# TopLevel.net
KiCad netlist of a schematic drawn in Altium Designer
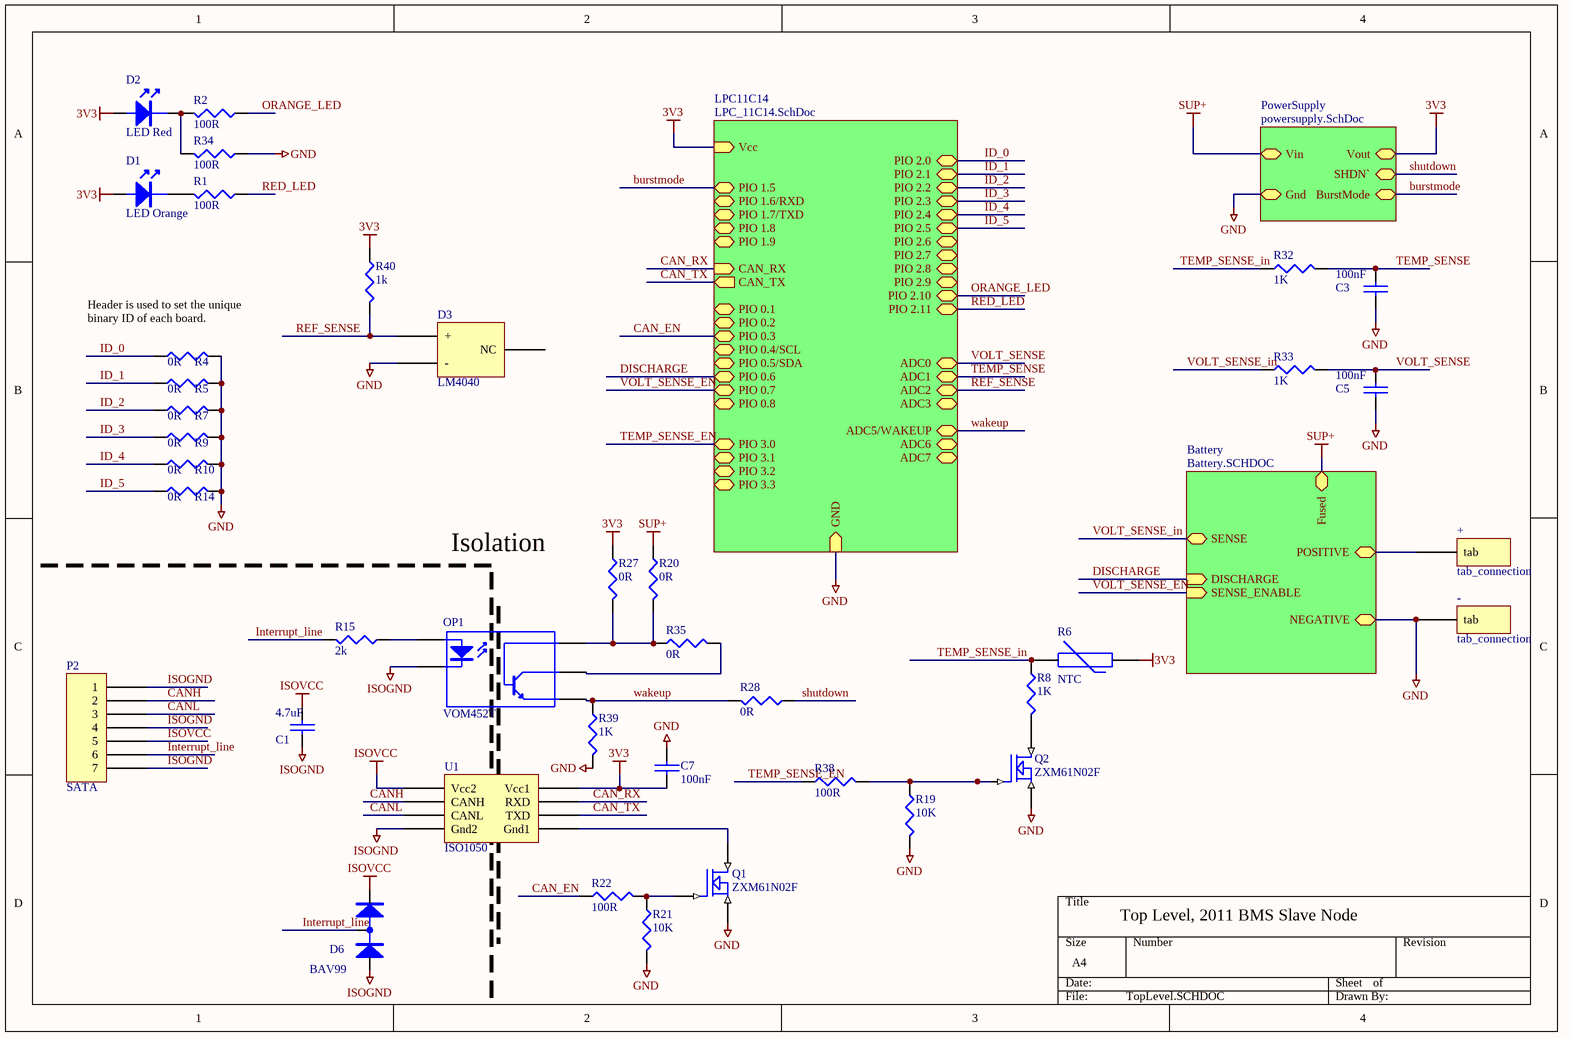
[diagram p0: TopLevel.SCHDOC]

(export (version "E")
  (design (tool "Eeschema 10.0.6"))
  (components
    (comp (ref "+")
      (value "tab_connection")
      (footprint "tab_connect")
      (libsource (lib "BMS") (part "tab_connection"))
    )
    (comp (ref "-")
      (value "tab_connection")
      (footprint "tab_connect")
      (libsource (lib "BMS") (part "tab_connection"))
    )
    (comp (ref "C1")
      (value "4.7uF")
      (footprint "0805")
      (description "Capacitor")
      (libsource (lib "*") (part "CAP"))
    )
    (comp (ref "C3")
      (value "100nF")
      (footprint "0603")
      (description "Capacitor")
      (libsource (lib "*") (part "CAP"))
    )
    (comp (ref "C5")
      (value "100nF")
      (footprint "0603")
      (description "Capacitor")
      (libsource (lib "*") (part "CAP"))
    )
    (comp (ref "C7")
      (value "100nF")
      (footprint "0603")
      (description "Capacitor")
      (libsource (lib "*") (part "CAP"))
    )
    (comp (ref "D1") (value "LED Orange") (footprint "0603_LED") (libsource (lib "SUNSWIFTLIB") (part "LED")))
    (comp (ref "D2")
      (value "LED Red")
      (footprint "0603_LED")
      (libsource (lib "SunswiftLib20030312RR") (part "LED"))
    )
    (comp (ref "D3") (value "LM4040") (footprint "SOT23-3") (libsource (lib "BMS") (part "LM4040")))
    (comp (ref "D6")
      (value "BAV99")
      (footprint "BAV99")
      (description "diode, series connected")
      (libsource (lib "*") (part "DIODE SERIES 2"))
    )
    (comp (ref "OP1") (value "VOM452T") (footprint "VOM452T") (libsource (lib "BMS") (part "VOM452T")))
    (comp (ref "P2") (value "SATA") (footprint "47080-4005-SATA") (libsource (lib "BMS") (part "SATA")))
    (comp (ref "Q1")
      (value "ZXM61N02F")
      (footprint "SOT23-3")
      (description "1.7A, 20V N-Channel Enhancement mode FET")
      (libsource (lib "RCLDQ") (part "ZXM61N02F"))
    )
    (comp (ref "Q2")
      (value "ZXM61N02F")
      (footprint "SOT23-3")
      (description "1.7A, 20V N-Channel Enhancement mode FET")
      (libsource (lib "RCLDQ") (part "ZXM61N02F"))
    )
    (comp (ref "R1")
      (value "100R")
      (footprint "0603")
      (description "Resistor")
      (libsource (lib "SunswiftLib20030312RR") (part "RES1"))
    )
    (comp (ref "R2")
      (value "100R")
      (footprint "0603")
      (description "Resistor")
      (libsource (lib "SunswiftLib20030312RR") (part "RES1"))
    )
    (comp (ref "R4")
      (value "0R")
      (footprint "0603")
      (description "Resistor")
      (libsource (lib "SUNSWIFTLIB") (part "RES1"))
    )
    (comp (ref "R5")
      (value "0R")
      (footprint "0603")
      (description "Resistor")
      (libsource (lib "SUNSWIFTLIB") (part "RES1"))
    )
    (comp (ref "R6")
      (value "NTC")
      (footprint "MHDR1X2")
      (description "Thermistor, NTC")
      (libsource (lib "RCLDQ") (part "NTC"))
    )
    (comp (ref "R7")
      (value "0R")
      (footprint "0603")
      (description "Resistor")
      (libsource (lib "SUNSWIFTLIB") (part "RES1"))
    )
    (comp (ref "R8")
      (value "1K")
      (footprint "0603")
      (description "Resistor")
      (libsource (lib "SUNSWIFTLIB") (part "RES1"))
    )
    (comp (ref "R9")
      (value "0R")
      (footprint "0603")
      (description "Resistor")
      (libsource (lib "SUNSWIFTLIB") (part "RES1"))
    )
    (comp (ref "R10")
      (value "0R")
      (footprint "0603")
      (description "Resistor")
      (libsource (lib "SUNSWIFTLIB") (part "RES1"))
    )
    (comp (ref "R14")
      (value "0R")
      (footprint "0603")
      (description "Resistor")
      (libsource (lib "SUNSWIFTLIB") (part "RES1"))
    )
    (comp (ref "R15")
      (value "2k")
      (footprint "0603")
      (description "Resistor")
      (libsource (lib "RCLDQ") (part "RES1"))
    )
    (comp (ref "R19")
      (value "10K")
      (footprint "0603")
      (description "Resistor")
      (libsource (lib "SUNSWIFTLIB") (part "RES1"))
    )
    (comp (ref "R20")
      (value "0R")
      (footprint "0603")
      (description "Resistor")
      (libsource (lib "RCLDQ") (part "RES1"))
    )
    (comp (ref "R21")
      (value "10K")
      (footprint "0603")
      (description "Resistor")
      (libsource (lib "SUNSWIFTLIB") (part "RES1"))
    )
    (comp (ref "R22")
      (value "100R")
      (footprint "0603")
      (description "Resistor")
      (libsource (lib "SUNSWIFTLIB") (part "RES1"))
    )
    (comp (ref "R27")
      (value "0R")
      (footprint "0603")
      (description "Resistor")
      (libsource (lib "RCLDQ") (part "RES1"))
    )
    (comp (ref "R28")
      (value "0R")
      (footprint "0603")
      (description "Resistor")
      (libsource (lib "RCLDQ") (part "RES1"))
    )
    (comp (ref "R32")
      (value "1K")
      (footprint "0603")
      (description "Resistor")
      (libsource (lib "SUNSWIFTLIB") (part "RES1"))
    )
    (comp (ref "R33")
      (value "1K")
      (footprint "0603")
      (description "Resistor")
      (libsource (lib "SUNSWIFTLIB") (part "RES1"))
    )
    (comp (ref "R34")
      (value "100R")
      (footprint "0603")
      (description "Resistor")
      (libsource (lib "SunswiftLib20030312RR") (part "RES1"))
    )
    (comp (ref "R35")
      (value "0R")
      (footprint "0603")
      (description "Resistor")
      (libsource (lib "RCLDQ") (part "RES1"))
    )
    (comp (ref "R38")
      (value "100R")
      (footprint "0603")
      (description "Resistor")
      (libsource (lib "SUNSWIFTLIB") (part "RES1"))
    )
    (comp (ref "R39")
      (value "1K")
      (footprint "0603")
      (description "Resistor")
      (libsource (lib "RCLDQ") (part "RES1"))
    )
    (comp (ref "R40")
      (value "1k")
      (footprint "0603")
      (description "Resistor")
      (libsource (lib "RCLDQ") (part "RES1"))
    )
    (comp (ref "U1") (value "ISO1050") (footprint "SOP8") (libsource (lib "BMS") (part "ISO1050")))
  )
  (nets
    (net (code "4") (name "/CANH") (class "Default")
      (node (ref "P2") (pin "2") (pinfunction "2_2") (pintype "passive"))
      (node (ref "U1") (pin "7") (pinfunction "CANH_7") (pintype "passive"))
    )
    (net (code "5") (name "/CANL") (class "Default")
      (node (ref "P2") (pin "3") (pinfunction "3_3") (pintype "passive"))
      (node (ref "U1") (pin "6") (pinfunction "CANL_6") (pintype "passive"))
    )
    (net (code "6") (name "/CAN_EN") (class "Default")
      (node (ref "R22") (pin "1") (pinfunction "1_1") (pintype "passive"))
    )
    (net (code "7") (name "/CAN_RX") (class "Default")
      (node (ref "U1") (pin "2") (pinfunction "RXD_2") (pintype "passive"))
    )
    (net (code "8") (name "/CAN_TX") (class "Default")
      (node (ref "U1") (pin "3") (pinfunction "TXD_3") (pintype "passive"))
    )
    (net (code "10") (name "/ID_0") (class "Default")
      (node (ref "R4") (pin "1") (pinfunction "1_1") (pintype "passive"))
    )
    (net (code "11") (name "/ID_1") (class "Default")
      (node (ref "R5") (pin "1") (pinfunction "1_1") (pintype "passive"))
    )
    (net (code "12") (name "/ID_2") (class "Default")
      (node (ref "R7") (pin "1") (pinfunction "1_1") (pintype "passive"))
    )
    (net (code "13") (name "/ID_3") (class "Default")
      (node (ref "R9") (pin "1") (pinfunction "1_1") (pintype "passive"))
    )
    (net (code "14") (name "/ID_4") (class "Default")
      (node (ref "R10") (pin "1") (pinfunction "1_1") (pintype "passive"))
    )
    (net (code "15") (name "/ID_5") (class "Default")
      (node (ref "R14") (pin "1") (pinfunction "1_1") (pintype "passive"))
    )
    (net (code "16") (name "/Interrupt_line") (class "Default")
      (node (ref "D6") (pin "C") (pinfunction "C_C") (pintype "passive"))
      (node (ref "P2") (pin "6") (pinfunction "6_6") (pintype "passive"))
      (node (ref "R15") (pin "2") (pinfunction "2_2") (pintype "passive"))
    )
    (net (code "17") (name "/ORANGE_LED") (class "Default")
      (node (ref "R2") (pin "1") (pinfunction "1_1") (pintype "passive"))
    )
    (net (code "34") (name "/POSITIVE") (class "Default")
      (node (ref "+") (pin "0") (pinfunction "tab_0") (pintype "passive"))
    )
    (net (code "35") (name "/RED_LED") (class "Default")
      (node (ref "R1") (pin "1") (pinfunction "1_1") (pintype "passive"))
    )
    (net (code "36") (name "/REF_SENSE") (class "Default")
      (node (ref "D3") (pin "1") (pinfunction "+_1") (pintype "passive"))
      (node (ref "R40") (pin "2") (pinfunction "2_2") (pintype "passive"))
    )
    (net (code "37") (name "/TEMP_SENSE") (class "Default")
      (node (ref "C3") (pin "1") (pinfunction "1_1") (pintype "passive"))
      (node (ref "R32") (pin "2") (pinfunction "2_2") (pintype "passive"))
    )
    (net (code "38") (name "/TEMP_SENSE_EN") (class "Default")
      (node (ref "R38") (pin "1") (pinfunction "1_1") (pintype "passive"))
    )
    (net (code "39") (name "/TEMP_SENSE_in") (class "Default")
      (node (ref "R32") (pin "1") (pinfunction "1_1") (pintype "passive"))
      (node (ref "R6") (pin "1") (pinfunction "1_1") (pintype "passive"))
      (node (ref "R8") (pin "1") (pinfunction "1_1") (pintype "passive"))
    )
    (net (code "40") (name "/VOLT_SENSE") (class "Default")
      (node (ref "C5") (pin "1") (pinfunction "1_1") (pintype "passive"))
      (node (ref "R33") (pin "2") (pinfunction "2_2") (pintype "passive"))
    )
    (net (code "42") (name "/VOLT_SENSE_in") (class "Default")
      (node (ref "R33") (pin "1") (pinfunction "1_1") (pintype "passive"))
    )
    (net (code "44") (name "/shutdown") (class "Default")
      (node (ref "R28") (pin "1") (pinfunction "1_1") (pintype "passive"))
    )
    (net (code "45") (name "/wakeup") (class "Default")
      (node (ref "OP1") (pin "4") (pinfunction "E_4") (pintype "passive"))
      (node (ref "R28") (pin "2") (pinfunction "2_2") (pintype "passive"))
      (node (ref "R39") (pin "1") (pinfunction "1_1") (pintype "passive"))
    )
    (net (code "46") (name "3V3") (class "Default")
      (node (ref "C7") (pin "1") (pinfunction "1_1") (pintype "passive"))
      (node (ref "D1") (pin "A") (pinfunction "A_A") (pintype "passive"))
      (node (ref "D2") (pin "A") (pinfunction "A_A") (pintype "passive"))
      (node (ref "R27") (pin "1") (pinfunction "1_1") (pintype "passive"))
      (node (ref "R40") (pin "1") (pinfunction "1_1") (pintype "passive"))
      (node (ref "R6") (pin "2") (pinfunction "2_2") (pintype "passive"))
      (node (ref "U1") (pin "1") (pinfunction "Vcc1_1") (pintype "passive"))
    )
    (net (code "47") (name "GND") (class "Default")
      (node (ref "-") (pin "0") (pinfunction "tab_0") (pintype "passive"))
      (node (ref "C3") (pin "2") (pinfunction "2_2") (pintype "passive"))
      (node (ref "C5") (pin "2") (pinfunction "2_2") (pintype "passive"))
      (node (ref "C7") (pin "2") (pinfunction "2_2") (pintype "passive"))
      (node (ref "D3") (pin "2") (pinfunction "-_2") (pintype "passive"))
      (node (ref "Q1") (pin "2") (pinfunction "S_2") (pintype "input"))
      (node (ref "Q2") (pin "2") (pinfunction "S_2") (pintype "input"))
      (node (ref "R10") (pin "2") (pinfunction "2_2") (pintype "passive"))
      (node (ref "R14") (pin "2") (pinfunction "2_2") (pintype "passive"))
      (node (ref "R19") (pin "2") (pinfunction "2_2") (pintype "passive"))
      (node (ref "R21") (pin "2") (pinfunction "2_2") (pintype "passive"))
      (node (ref "R34") (pin "1") (pinfunction "1_1") (pintype "passive"))
      (node (ref "R39") (pin "2") (pinfunction "2_2") (pintype "passive"))
      (node (ref "R4") (pin "2") (pinfunction "2_2") (pintype "passive"))
      (node (ref "R5") (pin "2") (pinfunction "2_2") (pintype "passive"))
      (node (ref "R7") (pin "2") (pinfunction "2_2") (pintype "passive"))
      (node (ref "R9") (pin "2") (pinfunction "2_2") (pintype "passive"))
    )
    (net (code "48") (name "ISOGND") (class "Default")
      (node (ref "C1") (pin "2") (pinfunction "2_2") (pintype "passive"))
      (node (ref "D6") (pin "A") (pinfunction "A_A") (pintype "passive"))
      (node (ref "OP1") (pin "3") (pinfunction "K_3") (pintype "passive"))
      (node (ref "P2") (pin "1") (pinfunction "1_1") (pintype "passive"))
      (node (ref "P2") (pin "4") (pinfunction "4_4") (pintype "passive"))
      (node (ref "P2") (pin "7") (pinfunction "7_7") (pintype "passive"))
      (node (ref "U1") (pin "5") (pinfunction "Gnd2_5") (pintype "passive"))
    )
    (net (code "49") (name "ISOVCC") (class "Default")
      (node (ref "C1") (pin "1") (pinfunction "1_1") (pintype "passive"))
      (node (ref "D6") (pin "K") (pinfunction "K_K") (pintype "passive"))
      (node (ref "P2") (pin "5") (pinfunction "5_5") (pintype "passive"))
      (node (ref "U1") (pin "8") (pinfunction "Vcc2_8") (pintype "passive"))
    )
    (net (code "50") (name "Net-(D1-PadK)") (class "Default")
      (node (ref "D1") (pin "K") (pinfunction "K_K") (pintype "passive"))
      (node (ref "R1") (pin "2") (pinfunction "2_2") (pintype "passive"))
    )
    (net (code "51") (name "Net-(D2-PadK)") (class "Default")
      (node (ref "D2") (pin "K") (pinfunction "K_K") (pintype "passive"))
      (node (ref "R2") (pin "2") (pinfunction "2_2") (pintype "passive"))
      (node (ref "R34") (pin "2") (pinfunction "2_2") (pintype "passive"))
    )
    (net (code "52") (name "Net-(OP1-A)") (class "Default")
      (node (ref "OP1") (pin "1") (pinfunction "A_1") (pintype "passive"))
      (node (ref "R15") (pin "1") (pinfunction "1_1") (pintype "passive"))
    )
    (net (code "53") (name "Net-(OP1-C-Pad5)") (class "Default")
      (node (ref "OP1") (pin "5") (pinfunction "C_5") (pintype "passive"))
      (node (ref "R35") (pin "2") (pinfunction "2_2") (pintype "passive"))
    )
    (net (code "54") (name "Net-(OP1-C-Pad6)") (class "Default")
      (node (ref "OP1") (pin "6") (pinfunction "C_6") (pintype "passive"))
      (node (ref "R20") (pin "2") (pinfunction "2_2") (pintype "passive"))
      (node (ref "R27") (pin "2") (pinfunction "2_2") (pintype "passive"))
      (node (ref "R35") (pin "1") (pinfunction "1_1") (pintype "passive"))
    )
    (net (code "55") (name "Net-(Q1-D)") (class "Default")
      (node (ref "Q1") (pin "3") (pinfunction "D_3") (pintype "input"))
      (node (ref "U1") (pin "4") (pinfunction "Gnd1_4") (pintype "passive"))
    )
    (net (code "56") (name "Net-(Q1-G)") (class "Default")
      (node (ref "Q1") (pin "1") (pinfunction "G_1") (pintype "input"))
      (node (ref "R21") (pin "1") (pinfunction "1_1") (pintype "passive"))
      (node (ref "R22") (pin "2") (pinfunction "2_2") (pintype "passive"))
    )
    (net (code "57") (name "Net-(Q2-D)") (class "Default")
      (node (ref "Q2") (pin "3") (pinfunction "D_3") (pintype "input"))
      (node (ref "R8") (pin "2") (pinfunction "2_2") (pintype "passive"))
    )
    (net (code "58") (name "Net-(Q2-G)") (class "Default")
      (node (ref "Q2") (pin "1") (pinfunction "G_1") (pintype "input"))
      (node (ref "R19") (pin "1") (pinfunction "1_1") (pintype "passive"))
      (node (ref "R38") (pin "2") (pinfunction "2_2") (pintype "passive"))
    )
    (net (code "59") (name "SUP+") (class "Default")
      (node (ref "R20") (pin "1") (pinfunction "1_1") (pintype "passive"))
    )
    (net (code "60") (name "unconnected-(D3-NC-Pad3)") (class "Default")
      (node (ref "D3") (pin "3") (pinfunction "NC_3") (pintype "passive"))
    )
  )
)
